# 2_2_128x32_OLED-SPI-DRO-FTDI-6.net
KiCad netlist of a schematic drawn in EAGLE
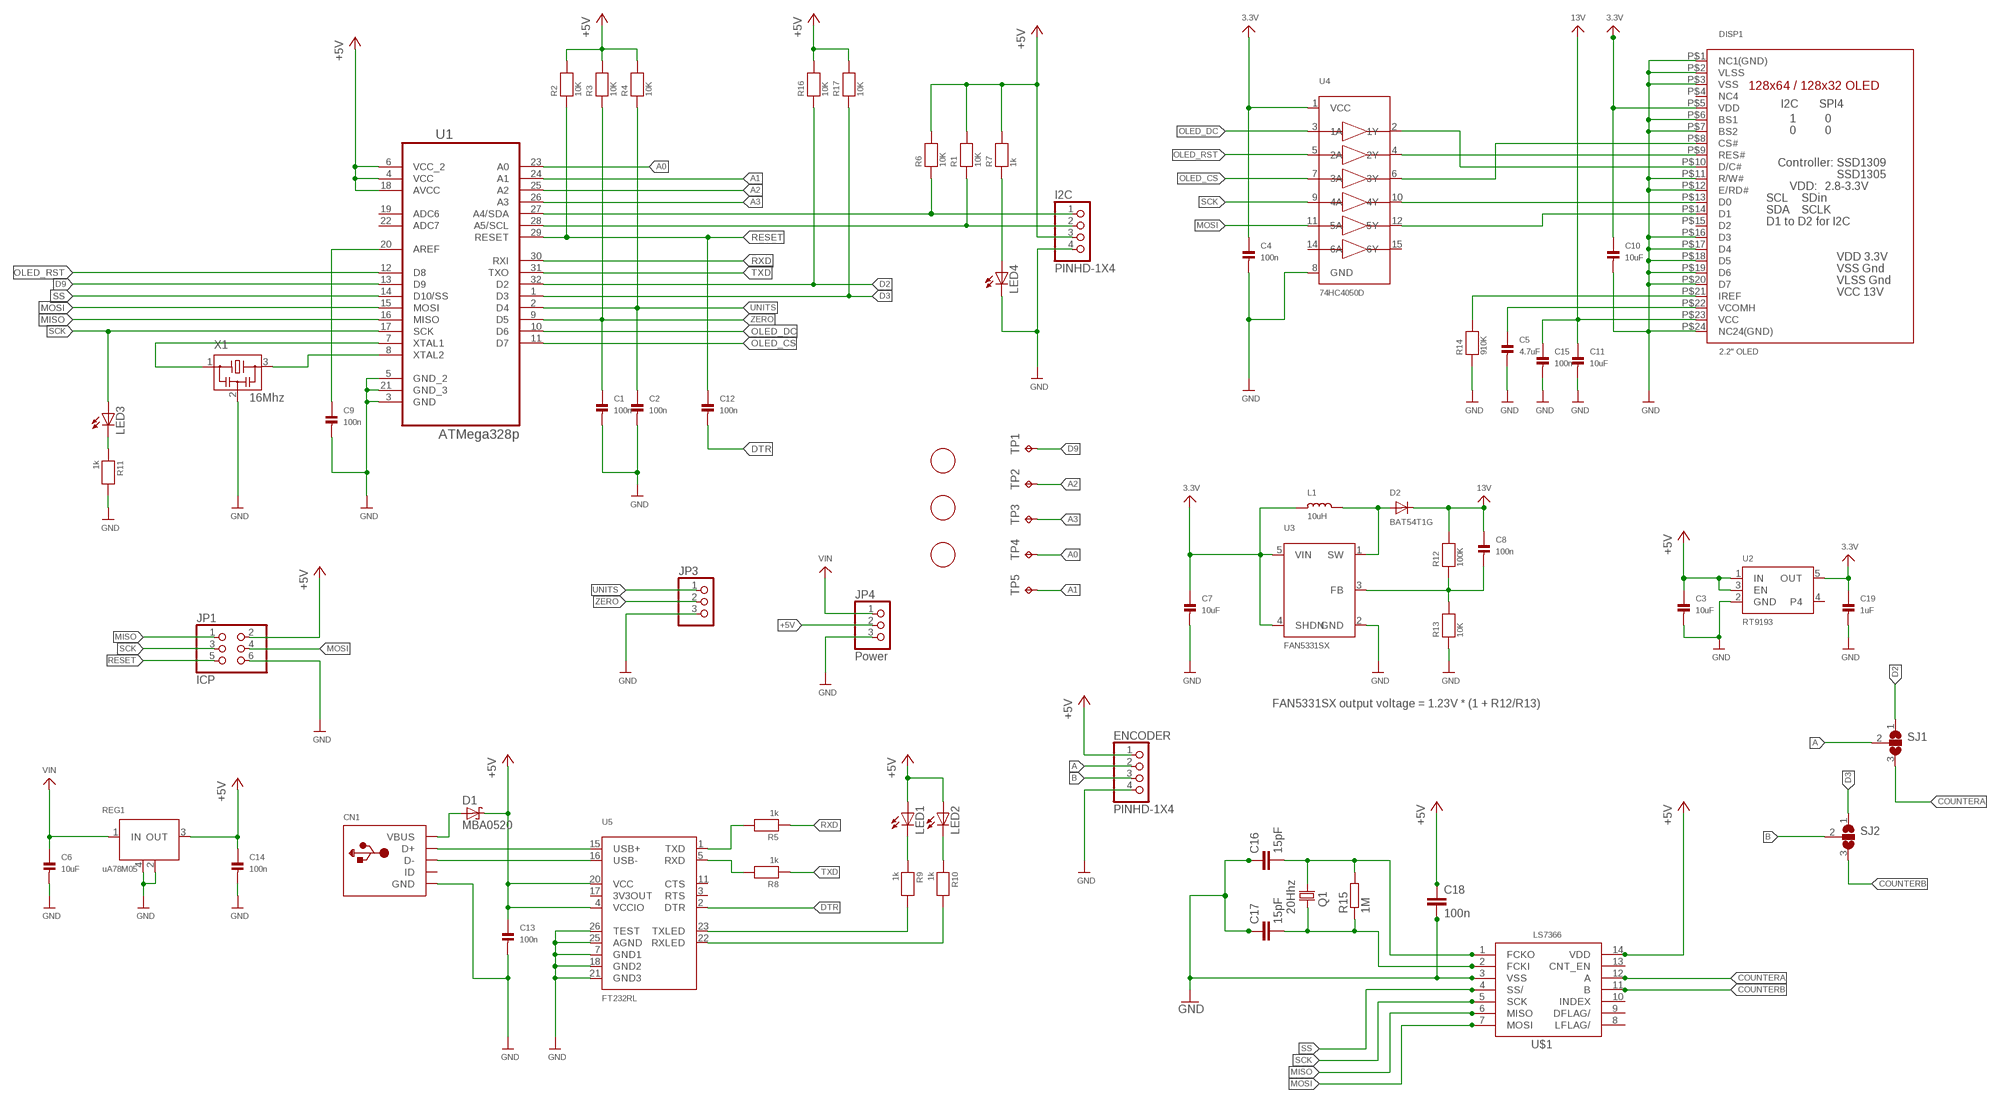
[diagram p0: schematic, sheet 1]

(export (version "E")
  (design (tool "Eeschema 10.0.6"))
  (components
    (comp (ref "C1")
      (value "100n")
      (footprint "eagle-import:0805")
      (libsource (lib "eagle-import") (part "CAP_CERAMIC0805"))
    )
    (comp (ref "C2")
      (value "100n")
      (footprint "eagle-import:0805")
      (libsource (lib "eagle-import") (part "CAP_CERAMIC0805"))
    )
    (comp (ref "C3")
      (value "10uF")
      (footprint "eagle-import:0805")
      (libsource (lib "eagle-import") (part "CAP_CERAMIC0805"))
    )
    (comp (ref "C4")
      (value "100n")
      (footprint "eagle-import:0805")
      (libsource (lib "eagle-import") (part "CAP_CERAMIC0805"))
    )
    (comp (ref "C5")
      (value "4.7uF")
      (footprint "eagle-import:0805")
      (libsource (lib "eagle-import") (part "CAP_CERAMIC0805"))
    )
    (comp (ref "C6")
      (value "10uF")
      (footprint "eagle-import:0805")
      (libsource (lib "eagle-import") (part "CAP_CERAMIC0805"))
    )
    (comp (ref "C7")
      (value "10uF")
      (footprint "eagle-import:0805")
      (libsource (lib "eagle-import") (part "CAP_CERAMIC0805"))
    )
    (comp (ref "C8")
      (value "100n")
      (footprint "eagle-import:0805")
      (libsource (lib "eagle-import") (part "CAP_CERAMIC0805"))
    )
    (comp (ref "C9")
      (value "100n")
      (footprint "eagle-import:0805")
      (libsource (lib "eagle-import") (part "CAP_CERAMIC0805"))
    )
    (comp (ref "C10")
      (value "10uF")
      (footprint "eagle-import:0805")
      (libsource (lib "eagle-import") (part "CAP_CERAMIC0805"))
    )
    (comp (ref "C11")
      (value "10uF")
      (footprint "eagle-import:0805")
      (libsource (lib "eagle-import") (part "CAP_CERAMIC0805"))
    )
    (comp (ref "C12")
      (value "100n")
      (footprint "eagle-import:0805")
      (libsource (lib "eagle-import") (part "CAP_CERAMIC0805"))
    )
    (comp (ref "C13")
      (value "100n")
      (footprint "eagle-import:0805")
      (libsource (lib "eagle-import") (part "CAP_CERAMIC0805"))
    )
    (comp (ref "C14")
      (value "100n")
      (footprint "eagle-import:0805")
      (libsource (lib "eagle-import") (part "CAP_CERAMIC0805"))
    )
    (comp (ref "C15")
      (value "100n")
      (footprint "eagle-import:0805")
      (libsource (lib "eagle-import") (part "CAP_CERAMIC0805"))
    )
    (comp (ref "C16")
      (value "15pF")
      (footprint "eagle-import:C0805")
      (libsource (lib "eagle-import") (part "C-EUC0805"))
    )
    (comp (ref "C17")
      (value "15pF")
      (footprint "eagle-import:C0805")
      (libsource (lib "eagle-import") (part "C-EUC0805"))
    )
    (comp (ref "C18")
      (value "100n")
      (footprint "eagle-import:C0805")
      (libsource (lib "eagle-import") (part "C-EUC0805"))
    )
    (comp (ref "C19")
      (value "1uF")
      (footprint "eagle-import:0805")
      (libsource (lib "eagle-import") (part "CAP_CERAMIC0805"))
    )
    (comp (ref "CN1")
      (value "USBMINIB")
      (footprint "eagle-import:USB-MINIB")
      (libsource (lib "eagle-import") (part "USBMINIB"))
    )
    (comp (ref "D1")
      (value "MBA0520")
      (footprint "eagle-import:SOD123")
      (libsource (lib "eagle-import") (part "MBR0520"))
    )
    (comp (ref "D2")
      (value "BAT54T1G")
      (footprint "eagle-import:SOD-123")
      (libsource (lib "eagle-import") (part "DIODESOD-123"))
    )
    (comp (ref "DISP1")
      (value "2.2\" OLED")
      (footprint "eagle-import:1.5-128X64-TOP-CONTACT")
      (libsource (lib "eagle-import") (part "1.5-128X64-OLED"))
    )
    (comp (ref "ENCODER")
      (value "PINHD-1X4")
      (footprint "eagle-import:1X04-BIG")
      (libsource (lib "eagle-import") (part "PINHD-1X4"))
    )
    (comp (ref "I2C")
      (value "PINHD-1X4")
      (footprint "eagle-import:1X04-BIG")
      (libsource (lib "eagle-import") (part "PINHD-1X4"))
    )
    (comp (ref "JP1")
      (value "ICP")
      (footprint "eagle-import:2X03")
      (libsource (lib "eagle-import") (part "PINHD-2X3"))
    )
    (comp (ref "JP3")
      (value "PINHD-1X3")
      (footprint "eagle-import:1X03")
      (libsource (lib "eagle-import") (part "PINHD-1X3"))
    )
    (comp (ref "JP4")
      (value "Power")
      (footprint "eagle-import:1X03")
      (libsource (lib "eagle-import") (part "PINHD-1X3"))
    )
    (comp (ref "L1")
      (value "10uH")
      (footprint "eagle-import:INDUCTOR_1007")
      (libsource (lib "eagle-import") (part "INDUCTOR"))
    )
    (comp (ref "LED1")
      (value "LEDCHIPLED_0805")
      (footprint "eagle-import:CHIPLED_0805")
      (libsource (lib "eagle-import") (part "LEDCHIPLED_0805"))
    )
    (comp (ref "LED2")
      (value "LEDCHIPLED_0805")
      (footprint "eagle-import:CHIPLED_0805")
      (libsource (lib "eagle-import") (part "LEDCHIPLED_0805"))
    )
    (comp (ref "LED3")
      (value "LEDCHIPLED_0805")
      (footprint "eagle-import:CHIPLED_0805")
      (libsource (lib "eagle-import") (part "LEDCHIPLED_0805"))
    )
    (comp (ref "LED4")
      (value "LEDCHIPLED_0805")
      (footprint "eagle-import:CHIPLED_0805")
      (libsource (lib "eagle-import") (part "LEDCHIPLED_0805"))
    )
    (comp (ref "Q1")
      (value "20Hhz")
      (footprint "eagle-import:F6-XTAL")
      (libsource (lib "eagle-import") (part "F6-CRYSTAL"))
    )
    (comp (ref "R1")
      (value "10K")
      (footprint "eagle-import:0805")
      (libsource (lib "eagle-import") (part "RESISTOR0805"))
    )
    (comp (ref "R2")
      (value "10K")
      (footprint "eagle-import:0805")
      (libsource (lib "eagle-import") (part "RESISTOR0805"))
    )
    (comp (ref "R3")
      (value "10K")
      (footprint "eagle-import:0805")
      (libsource (lib "eagle-import") (part "RESISTOR0805"))
    )
    (comp (ref "R4")
      (value "10K")
      (footprint "eagle-import:0805")
      (libsource (lib "eagle-import") (part "RESISTOR0805"))
    )
    (comp (ref "R5")
      (value "1k")
      (footprint "eagle-import:0805")
      (libsource (lib "eagle-import") (part "RESISTOR0805"))
    )
    (comp (ref "R6")
      (value "10K")
      (footprint "eagle-import:0805")
      (libsource (lib "eagle-import") (part "RESISTOR0805"))
    )
    (comp (ref "R7")
      (value "1k")
      (footprint "eagle-import:0805")
      (libsource (lib "eagle-import") (part "RESISTOR0805"))
    )
    (comp (ref "R8")
      (value "1k")
      (footprint "eagle-import:0805")
      (libsource (lib "eagle-import") (part "RESISTOR0805"))
    )
    (comp (ref "R9")
      (value "1k")
      (footprint "eagle-import:0805")
      (libsource (lib "eagle-import") (part "RESISTOR0805"))
    )
    (comp (ref "R10")
      (value "1k")
      (footprint "eagle-import:0805")
      (libsource (lib "eagle-import") (part "RESISTOR0805"))
    )
    (comp (ref "R11")
      (value "1k")
      (footprint "eagle-import:0805")
      (libsource (lib "eagle-import") (part "RESISTOR0805"))
    )
    (comp (ref "R12")
      (value "100K")
      (footprint "eagle-import:0805")
      (libsource (lib "eagle-import") (part "RESISTOR0805"))
    )
    (comp (ref "R13")
      (value "10K")
      (footprint "eagle-import:0805")
      (libsource (lib "eagle-import") (part "RESISTOR0805"))
    )
    (comp (ref "R14")
      (value "910K")
      (footprint "eagle-import:0805")
      (libsource (lib "eagle-import") (part "RESISTOR0805"))
    )
    (comp (ref "R15")
      (value "1M")
      (footprint "eagle-import:M0805")
      (libsource (lib "eagle-import") (part "R-EU_M0805"))
    )
    (comp (ref "R16")
      (value "10K")
      (footprint "eagle-import:0805")
      (libsource (lib "eagle-import") (part "RESISTOR0805"))
    )
    (comp (ref "R17")
      (value "10K")
      (footprint "eagle-import:0805")
      (libsource (lib "eagle-import") (part "RESISTOR0805"))
    )
    (comp (ref "REG1")
      (value "uA78M05")
      (footprint "eagle-import:UA78M05")
      (libsource (lib "eagle-import") (part "UA78M05"))
    )
    (comp (ref "SJ1")
      (value "SJ2W")
      (footprint "eagle-import:SJ_2")
      (libsource (lib "eagle-import") (part "SJ2W"))
    )
    (comp (ref "SJ2")
      (value "SJ2W")
      (footprint "eagle-import:SJ_2")
      (libsource (lib "eagle-import") (part "SJ2W"))
    )
    (comp (ref "TP1")
      (value "TPTP08R")
      (footprint "eagle-import:TP08R")
      (libsource (lib "eagle-import") (part "TPTP08R"))
    )
    (comp (ref "TP2")
      (value "TPTP08R")
      (footprint "eagle-import:TP08R")
      (libsource (lib "eagle-import") (part "TPTP08R"))
    )
    (comp (ref "TP3")
      (value "TPTP08R")
      (footprint "eagle-import:TP08R")
      (libsource (lib "eagle-import") (part "TPTP08R"))
    )
    (comp (ref "TP4")
      (value "TPTP08R")
      (footprint "eagle-import:TP08R")
      (libsource (lib "eagle-import") (part "TPTP08R"))
    )
    (comp (ref "TP5")
      (value "TPTP08R")
      (footprint "eagle-import:TP08R")
      (libsource (lib "eagle-import") (part "TPTP08R"))
    )
    (comp (ref "U$1")
      (value "LS7366")
      (footprint "eagle-import:SO14")
      (libsource (lib "eagle-import") (part "LS7366"))
    )
    (comp (ref "U$2")
      (value "FIDUCIAL")
      (footprint "eagle-import:FIDUCIAL_1MM")
      (libsource (lib "eagle-import") (part "FIDUCIAL"))
    )
    (comp (ref "U$6")
      (value "FIDUCIAL")
      (footprint "eagle-import:FIDUCIAL_1MM")
      (libsource (lib "eagle-import") (part "FIDUCIAL"))
    )
    (comp (ref "U$28")
      (value "FIDUCIAL")
      (footprint "eagle-import:FIDUCIAL_1MM")
      (libsource (lib "eagle-import") (part "FIDUCIAL"))
    )
    (comp (ref "U1")
      (value "ATMega328p")
      (footprint "eagle-import:TQFP-32")
      (libsource (lib "eagle-import") (part "ATMEGA328P-AU"))
    )
    (comp (ref "U2")
      (value "RT9193")
      (footprint "eagle-import:SOT23-5")
      (libsource (lib "eagle-import") (part "VREG_SOT23-5"))
    )
    (comp (ref "U3")
      (value "FAN5331SX")
      (footprint "eagle-import:SOT23-5")
      (libsource (lib "eagle-import") (part "FAN5331"))
    )
    (comp (ref "U4")
      (value "74HC4050D")
      (footprint "eagle-import:SOIC16")
      (libsource (lib "eagle-import") (part "74HC4050D"))
    )
    (comp (ref "U5")
      (value "FT232RL")
      (footprint "eagle-import:SSOP28DB")
      (libsource (lib "eagle-import") (part "FT232RLSSOP28"))
    )
    (comp (ref "X1")
      (value "16Mhz")
      (footprint "eagle-import:CSTCE-CRYSTAL-OSC")
      (libsource (lib "eagle-import") (part "CSTCE-CRYSTAL-OSC"))
    )
  )
  (nets
    (net (code "1") (name "+5V") (class "Default")
      (node (ref "C13") (pin "1") (pinfunction "P$1_1") (pintype "passive"))
      (node (ref "C14") (pin "1") (pinfunction "P$1_1") (pintype "passive"))
      (node (ref "C18") (pin "1") (pinfunction "1_1") (pintype "passive"))
      (node (ref "C3") (pin "1") (pinfunction "P$1_1") (pintype "passive"))
      (node (ref "D1") (pin "C") (pinfunction "C_C") (pintype "passive"))
      (node (ref "ENCODER") (pin "1") (pinfunction "1_1") (pintype "passive"))
      (node (ref "I2C") (pin "3") (pinfunction "3_3") (pintype "passive"))
      (node (ref "JP1") (pin "2") (pinfunction "2_2") (pintype "passive"))
      (node (ref "JP4") (pin "2") (pinfunction "2_2") (pintype "passive"))
      (node (ref "LED1") (pin "A") (pinfunction "A_A") (pintype "passive"))
      (node (ref "LED2") (pin "A") (pinfunction "A_A") (pintype "passive"))
      (node (ref "R1") (pin "2") (pinfunction "2_2") (pintype "passive"))
      (node (ref "R16") (pin "2") (pinfunction "2_2") (pintype "passive"))
      (node (ref "R17") (pin "2") (pinfunction "2_2") (pintype "passive"))
      (node (ref "R2") (pin "2") (pinfunction "2_2") (pintype "passive"))
      (node (ref "R3") (pin "2") (pinfunction "2_2") (pintype "passive"))
      (node (ref "R4") (pin "2") (pinfunction "2_2") (pintype "passive"))
      (node (ref "R6") (pin "2") (pinfunction "2_2") (pintype "passive"))
      (node (ref "R7") (pin "2") (pinfunction "2_2") (pintype "passive"))
      (node (ref "REG1") (pin "3") (pinfunction "OUT_3") (pintype "passive"))
      (node (ref "U$1") (pin "14") (pinfunction "VDD_14") (pintype "power_in"))
      (node (ref "U1") (pin "18") (pinfunction "AVCC_18") (pintype "power_in"))
      (node (ref "U1") (pin "4") (pinfunction "VCC_4") (pintype "power_in"))
      (node (ref "U1") (pin "6") (pinfunction "VCC_2_6") (pintype "power_in"))
      (node (ref "U2") (pin "1") (pinfunction "IN_1") (pintype "bidirectional"))
      (node (ref "U2") (pin "3") (pinfunction "EN_3") (pintype "bidirectional"))
      (node (ref "U5") (pin "20") (pinfunction "VCC_20") (pintype "power_in"))
      (node (ref "U5") (pin "4") (pinfunction "VCCIO_4") (pintype "power_in"))
    )
    (net (code "2") (name "/3V3OUT") (class "Default")
      (node (ref "U5") (pin "17") (pinfunction "3V3OUT_17") (pintype "power_in"))
    )
    (net (code "3") (name "3.3V") (class "Default")
      (node (ref "C10") (pin "1") (pinfunction "P$1_1") (pintype "passive"))
      (node (ref "C19") (pin "1") (pinfunction "P$1_1") (pintype "passive"))
      (node (ref "C4") (pin "1") (pinfunction "P$1_1") (pintype "passive"))
      (node (ref "C7") (pin "1") (pinfunction "P$1_1") (pintype "passive"))
      (node (ref "DISP1") (pin "P$5") (pinfunction "VDD_P$5") (pintype "power_in"))
      (node (ref "L1") (pin "P$1") (pinfunction "1_P$1") (pintype "passive"))
      (node (ref "U2") (pin "5") (pinfunction "OUT_5") (pintype "bidirectional"))
      (node (ref "U3") (pin "4") (pinfunction "SHDN_4") (pintype "bidirectional"))
      (node (ref "U3") (pin "5") (pinfunction "VIN_5") (pintype "bidirectional"))
      (node (ref "U4") (pin "1") (pinfunction "VCC_1") (pintype "bidirectional"))
    )
    (net (code "4") (name "13V") (class "Default")
      (node (ref "C11") (pin "1") (pinfunction "P$1_1") (pintype "passive"))
      (node (ref "C15") (pin "1") (pinfunction "P$1_1") (pintype "passive"))
      (node (ref "C8") (pin "1") (pinfunction "P$1_1") (pintype "passive"))
      (node (ref "D2") (pin "C") (pinfunction "C_C") (pintype "passive"))
      (node (ref "DISP1") (pin "P$23") (pinfunction "VCC_P$23") (pintype "power_in"))
      (node (ref "R12") (pin "2") (pinfunction "2_2") (pintype "passive"))
    )
    (net (code "5") (name "A") (class "Default")
      (node (ref "ENCODER") (pin "2") (pinfunction "2_2") (pintype "passive"))
      (node (ref "SJ1") (pin "2") (pinfunction "2_2") (pintype "passive"))
    )
    (net (code "6") (name "A0") (class "Default")
      (node (ref "TP4") (pin "TP") (pinfunction "TP_TP") (pintype "input"))
      (node (ref "U1") (pin "23") (pinfunction "A0_23") (pintype "bidirectional"))
    )
    (net (code "7") (name "A1") (class "Default")
      (node (ref "TP5") (pin "TP") (pinfunction "TP_TP") (pintype "input"))
      (node (ref "U1") (pin "24") (pinfunction "A1_24") (pintype "bidirectional"))
    )
    (net (code "8") (name "A2") (class "Default")
      (node (ref "TP2") (pin "TP") (pinfunction "TP_TP") (pintype "input"))
      (node (ref "U1") (pin "25") (pinfunction "A2_25") (pintype "bidirectional"))
    )
    (net (code "9") (name "A3") (class "Default")
      (node (ref "TP3") (pin "TP") (pinfunction "TP_TP") (pintype "input"))
      (node (ref "U1") (pin "26") (pinfunction "A3_26") (pintype "bidirectional"))
    )
    (net (code "10") (name "B") (class "Default")
      (node (ref "ENCODER") (pin "3") (pinfunction "3_3") (pintype "passive"))
      (node (ref "SJ2") (pin "2") (pinfunction "2_2") (pintype "passive"))
    )
    (net (code "11") (name "COUNTERA") (class "Default")
      (node (ref "SJ1") (pin "3") (pinfunction "3_3") (pintype "passive"))
      (node (ref "U$1") (pin "12") (pinfunction "A_12") (pintype "bidirectional"))
    )
    (net (code "12") (name "COUNTERB") (class "Default")
      (node (ref "SJ2") (pin "3") (pinfunction "3_3") (pintype "passive"))
      (node (ref "U$1") (pin "11") (pinfunction "B_11") (pintype "bidirectional"))
    )
    (net (code "13") (name "D2") (class "Default")
      (node (ref "R16") (pin "1") (pinfunction "1_1") (pintype "passive"))
      (node (ref "SJ1") (pin "1") (pinfunction "1_1") (pintype "passive"))
      (node (ref "U1") (pin "32") (pinfunction "D2_32") (pintype "bidirectional"))
    )
    (net (code "14") (name "D3") (class "Default")
      (node (ref "R17") (pin "1") (pinfunction "1_1") (pintype "passive"))
      (node (ref "SJ2") (pin "1") (pinfunction "1_1") (pintype "passive"))
      (node (ref "U1") (pin "1") (pinfunction "D3_1") (pintype "bidirectional"))
    )
    (net (code "15") (name "D9") (class "Default")
      (node (ref "TP1") (pin "TP") (pinfunction "TP_TP") (pintype "input"))
      (node (ref "U1") (pin "13") (pinfunction "D9_13") (pintype "bidirectional"))
    )
    (net (code "16") (name "DTR") (class "Default")
      (node (ref "C12") (pin "2") (pinfunction "P$2_2") (pintype "passive"))
      (node (ref "U5") (pin "2") (pinfunction "DTR_2") (pintype "bidirectional"))
    )
    (net (code "17") (name "GND") (class "Default")
      (node (ref "C1") (pin "2") (pinfunction "P$2_2") (pintype "passive"))
      (node (ref "C10") (pin "2") (pinfunction "P$2_2") (pintype "passive"))
      (node (ref "C11") (pin "2") (pinfunction "P$2_2") (pintype "passive"))
      (node (ref "C13") (pin "2") (pinfunction "P$2_2") (pintype "passive"))
      (node (ref "C14") (pin "2") (pinfunction "P$2_2") (pintype "passive"))
      (node (ref "C15") (pin "2") (pinfunction "P$2_2") (pintype "passive"))
      (node (ref "C16") (pin "1") (pinfunction "1_1") (pintype "passive"))
      (node (ref "C17") (pin "1") (pinfunction "1_1") (pintype "passive"))
      (node (ref "C18") (pin "2") (pinfunction "2_2") (pintype "passive"))
      (node (ref "C19") (pin "2") (pinfunction "P$2_2") (pintype "passive"))
      (node (ref "C2") (pin "2") (pinfunction "P$2_2") (pintype "passive"))
      (node (ref "C3") (pin "2") (pinfunction "P$2_2") (pintype "passive"))
      (node (ref "C4") (pin "2") (pinfunction "P$2_2") (pintype "passive"))
      (node (ref "C5") (pin "2") (pinfunction "P$2_2") (pintype "passive"))
      (node (ref "C6") (pin "2") (pinfunction "P$2_2") (pintype "passive"))
      (node (ref "C7") (pin "2") (pinfunction "P$2_2") (pintype "passive"))
      (node (ref "C9") (pin "2") (pinfunction "P$2_2") (pintype "passive"))
      (node (ref "CN1") (pin "GND") (pinfunction "GND_GND") (pintype "power_in"))
      (node (ref "DISP1") (pin "P$1") (pinfunction "NC1(GND)_P$1") (pintype "bidirectional"))
      (node (ref "DISP1") (pin "P$11") (pinfunction "R/W#_P$11") (pintype "bidirectional"))
      (node (ref "DISP1") (pin "P$12") (pinfunction "E/RD#_P$12") (pintype "bidirectional"))
      (node (ref "DISP1") (pin "P$16") (pinfunction "D3_P$16") (pintype "input"))
      (node (ref "DISP1") (pin "P$17") (pinfunction "D4_P$17") (pintype "input"))
      (node (ref "DISP1") (pin "P$18") (pinfunction "D5_P$18") (pintype "bidirectional"))
      (node (ref "DISP1") (pin "P$19") (pinfunction "D6_P$19") (pintype "bidirectional"))
      (node (ref "DISP1") (pin "P$2") (pinfunction "VLSS_P$2") (pintype "power_in"))
      (node (ref "DISP1") (pin "P$20") (pinfunction "D7_P$20") (pintype "bidirectional"))
      (node (ref "DISP1") (pin "P$24") (pinfunction "NC24(GND)_P$24") (pintype "bidirectional"))
      (node (ref "DISP1") (pin "P$3") (pinfunction "VSS_P$3") (pintype "power_in"))
      (node (ref "DISP1") (pin "P$6") (pinfunction "BS1_P$6") (pintype "bidirectional"))
      (node (ref "DISP1") (pin "P$7") (pinfunction "BS2_P$7") (pintype "bidirectional"))
      (node (ref "ENCODER") (pin "4") (pinfunction "4_4") (pintype "passive"))
      (node (ref "I2C") (pin "4") (pinfunction "4_4") (pintype "passive"))
      (node (ref "JP1") (pin "6") (pinfunction "6_6") (pintype "passive"))
      (node (ref "JP3") (pin "3") (pinfunction "3_3") (pintype "passive"))
      (node (ref "JP4") (pin "3") (pinfunction "3_3") (pintype "passive"))
      (node (ref "LED4") (pin "C") (pinfunction "C_C") (pintype "passive"))
      (node (ref "R11") (pin "2") (pinfunction "2_2") (pintype "passive"))
      (node (ref "R13") (pin "1") (pinfunction "1_1") (pintype "passive"))
      (node (ref "R14") (pin "1") (pinfunction "1_1") (pintype "passive"))
      (node (ref "REG1") (pin "2") (pinfunction "COMMON1_2") (pintype "passive"))
      (node (ref "REG1") (pin "4") (pinfunction "COMMON2_4") (pintype "passive"))
      (node (ref "U$1") (pin "3") (pinfunction "VSS_3") (pintype "power_in"))
      (node (ref "U1") (pin "21") (pinfunction "GND_3_21") (pintype "passive"))
      (node (ref "U1") (pin "3") (pinfunction "GND_3") (pintype "passive"))
      (node (ref "U1") (pin "5") (pinfunction "GND_2_5") (pintype "passive"))
      (node (ref "U2") (pin "2") (pinfunction "GND_2") (pintype "bidirectional"))
      (node (ref "U3") (pin "2") (pinfunction "GND_2") (pintype "bidirectional"))
      (node (ref "U4") (pin "8") (pinfunction "GND_8") (pintype "bidirectional"))
      (node (ref "U5") (pin "18") (pinfunction "GND2_18") (pintype "power_in"))
      (node (ref "U5") (pin "21") (pinfunction "GND3_21") (pintype "power_in"))
      (node (ref "U5") (pin "25") (pinfunction "AGND_25") (pintype "power_in"))
      (node (ref "U5") (pin "26") (pinfunction "TEST_26") (pintype "input"))
      (node (ref "U5") (pin "7") (pinfunction "GND1_7") (pintype "power_in"))
      (node (ref "X1") (pin "2") (pinfunction "2_2") (pintype "passive"))
    )
    (net (code "18") (name "MISO") (class "Default")
      (node (ref "JP1") (pin "1") (pinfunction "1_1") (pintype "passive"))
      (node (ref "U$1") (pin "6") (pinfunction "MISO_6") (pintype "output"))
      (node (ref "U1") (pin "16") (pinfunction "MISO_16") (pintype "bidirectional"))
    )
    (net (code "19") (name "MOSI") (class "Default")
      (node (ref "JP1") (pin "4") (pinfunction "4_4") (pintype "passive"))
      (node (ref "U$1") (pin "7") (pinfunction "MOSI_7") (pintype "input"))
      (node (ref "U1") (pin "15") (pinfunction "MOSI_15") (pintype "bidirectional"))
      (node (ref "U4") (pin "11") (pinfunction "5A_11") (pintype "bidirectional"))
    )
    (net (code "20") (name "Net-(C5-P$1)") (class "Default")
      (node (ref "C5") (pin "1") (pinfunction "P$1_1") (pintype "passive"))
      (node (ref "DISP1") (pin "P$22") (pinfunction "VCOMH_P$22") (pintype "bidirectional"))
    )
    (net (code "21") (name "Net-(C8-P$2)") (class "Default")
      (node (ref "C8") (pin "2") (pinfunction "P$2_2") (pintype "passive"))
      (node (ref "R12") (pin "1") (pinfunction "1_1") (pintype "passive"))
      (node (ref "R13") (pin "2") (pinfunction "2_2") (pintype "passive"))
      (node (ref "U3") (pin "3") (pinfunction "FB_3") (pintype "bidirectional"))
    )
    (net (code "22") (name "Net-(C9-P$1)") (class "Default")
      (node (ref "C9") (pin "1") (pinfunction "P$1_1") (pintype "passive"))
      (node (ref "U1") (pin "20") (pinfunction "AREF_20") (pintype "input"))
    )
    (net (code "23") (name "Net-(CN1-PadVBUS)") (class "Default")
      (node (ref "CN1") (pin "VBUS") (pinfunction "VBUS_VBUS") (pintype "power_in"))
      (node (ref "D1") (pin "A") (pinfunction "A_A") (pintype "passive"))
    )
    (net (code "24") (name "Net-(DISP1-CS#)") (class "Default")
      (node (ref "DISP1") (pin "P$8") (pinfunction "CS#_P$8") (pintype "bidirectional"))
      (node (ref "U4") (pin "6") (pinfunction "3Y_6") (pintype "bidirectional"))
    )
    (net (code "25") (name "Net-(DISP1-D0)") (class "Default")
      (node (ref "DISP1") (pin "P$13") (pinfunction "D0_P$13") (pintype "input"))
      (node (ref "U4") (pin "10") (pinfunction "4Y_10") (pintype "bidirectional"))
    )
    (net (code "26") (name "Net-(DISP1-D1)") (class "Default")
      (node (ref "DISP1") (pin "P$14") (pinfunction "D1_P$14") (pintype "input"))
      (node (ref "U4") (pin "12") (pinfunction "5Y_12") (pintype "bidirectional"))
    )
    (net (code "27") (name "Net-(DISP1-D{slash}C#)") (class "Default")
      (node (ref "DISP1") (pin "P$10") (pinfunction "D/C#_P$10") (pintype "bidirectional"))
      (node (ref "U4") (pin "2") (pinfunction "1Y_2") (pintype "bidirectional"))
    )
    (net (code "28") (name "Net-(DISP1-IREF)") (class "Default")
      (node (ref "DISP1") (pin "P$21") (pinfunction "IREF_P$21") (pintype "bidirectional"))
      (node (ref "R14") (pin "2") (pinfunction "2_2") (pintype "passive"))
    )
    (net (code "29") (name "Net-(DISP1-RES#)") (class "Default")
      (node (ref "DISP1") (pin "P$9") (pinfunction "RES#_P$9") (pintype "bidirectional"))
      (node (ref "U4") (pin "4") (pinfunction "2Y_4") (pintype "bidirectional"))
    )
    (net (code "30") (name "Net-(L1-2)") (class "Default")
      (node (ref "D2") (pin "A") (pinfunction "A_A") (pintype "passive"))
      (node (ref "L1") (pin "P$2") (pinfunction "2_P$2") (pintype "passive"))
      (node (ref "U3") (pin "1") (pinfunction "SW_1") (pintype "bidirectional"))
    )
    (net (code "31") (name "Net-(LED1-PadC)") (class "Default")
      (node (ref "LED1") (pin "C") (pinfunction "C_C") (pintype "passive"))
      (node (ref "R9") (pin "1") (pinfunction "1_1") (pintype "passive"))
    )
    (net (code "32") (name "Net-(LED2-PadC)") (class "Default")
      (node (ref "LED2") (pin "C") (pinfunction "C_C") (pintype "passive"))
      (node (ref "R10") (pin "1") (pinfunction "1_1") (pintype "passive"))
    )
    (net (code "33") (name "Net-(LED3-PadC)") (class "Default")
      (node (ref "LED3") (pin "C") (pinfunction "C_C") (pintype "passive"))
      (node (ref "R11") (pin "1") (pinfunction "1_1") (pintype "passive"))
    )
    (net (code "34") (name "Net-(LED4-PadA)") (class "Default")
      (node (ref "LED4") (pin "A") (pinfunction "A_A") (pintype "passive"))
      (node (ref "R7") (pin "1") (pinfunction "1_1") (pintype "passive"))
    )
    (net (code "35") (name "Net-(Q1-1)") (class "Default")
      (node (ref "C17") (pin "2") (pinfunction "2_2") (pintype "passive"))
      (node (ref "Q1") (pin "P$1") (pinfunction "1_P$1") (pintype "passive"))
      (node (ref "R15") (pin "1") (pinfunction "1_1") (pintype "passive"))
      (node (ref "U$1") (pin "2") (pinfunction "FCKI_2") (pintype "bidirectional"))
    )
    (net (code "36") (name "Net-(Q1-2)") (class "Default")
      (node (ref "C16") (pin "2") (pinfunction "2_2") (pintype "passive"))
      (node (ref "Q1") (pin "P$2") (pinfunction "2_P$2") (pintype "passive"))
      (node (ref "R15") (pin "2") (pinfunction "2_2") (pintype "passive"))
      (node (ref "U$1") (pin "1") (pinfunction "FCKO_1") (pintype "bidirectional"))
    )
    (net (code "37") (name "Net-(U1-A4{slash}SDA)") (class "Default")
      (node (ref "I2C") (pin "1") (pinfunction "1_1") (pintype "passive"))
      (node (ref "R6") (pin "1") (pinfunction "1_1") (pintype "passive"))
      (node (ref "U1") (pin "27") (pinfunction "A4/SDA_27") (pintype "bidirectional"))
    )
    (net (code "38") (name "Net-(U1-A5{slash}SCL)") (class "Default")
      (node (ref "I2C") (pin "2") (pinfunction "2_2") (pintype "passive"))
      (node (ref "R1") (pin "1") (pinfunction "1_1") (pintype "passive"))
      (node (ref "U1") (pin "28") (pinfunction "A5/SCL_28") (pintype "bidirectional"))
    )
    (net (code "39") (name "Net-(U1-XTAL1)") (class "Default")
      (node (ref "U1") (pin "7") (pinfunction "XTAL1_7") (pintype "bidirectional"))
      (node (ref "X1") (pin "1") (pinfunction "1_1") (pintype "passive"))
    )
    (net (code "40") (name "Net-(U1-XTAL2)") (class "Default")
      (node (ref "U1") (pin "8") (pinfunction "XTAL2_8") (pintype "bidirectional"))
      (node (ref "X1") (pin "3") (pinfunction "3_3") (pintype "passive"))
    )
    (net (code "41") (name "Net-(U5-RXD)") (class "Default")
      (node (ref "R8") (pin "2") (pinfunction "2_2") (pintype "passive"))
      (node (ref "U5") (pin "5") (pinfunction "RXD_5") (pintype "input"))
    )
    (net (code "42") (name "Net-(U5-RXLED)") (class "Default")
      (node (ref "R10") (pin "2") (pinfunction "2_2") (pintype "passive"))
      (node (ref "U5") (pin "22") (pinfunction "RXLED_22") (pintype "bidirectional"))
    )
    (net (code "43") (name "Net-(U5-TXD)") (class "Default")
      (node (ref "R5") (pin "2") (pinfunction "2_2") (pintype "passive"))
      (node (ref "U5") (pin "1") (pinfunction "TXD_1") (pintype "output"))
    )
    (net (code "44") (name "Net-(U5-TXLED)") (class "Default")
      (node (ref "R9") (pin "2") (pinfunction "2_2") (pintype "passive"))
      (node (ref "U5") (pin "23") (pinfunction "TXLED_23") (pintype "bidirectional"))
    )
    (net (code "45") (name "Net-(U5-USB+)") (class "Default")
      (node (ref "CN1") (pin "D+") (pinfunction "D+_D+") (pintype "bidirectional"))
      (node (ref "U5") (pin "15") (pinfunction "USB+_15") (pintype "bidirectional"))
    )
    (net (code "46") (name "Net-(U5-USB-)") (class "Default")
      (node (ref "CN1") (pin "D-") (pinfunction "D-_D-") (pintype "bidirectional"))
      (node (ref "U5") (pin "16") (pinfunction "USB-_16") (pintype "bidirectional"))
    )
    (net (code "47") (name "OLED_CS") (class "Default")
      (node (ref "U1") (pin "11") (pinfunction "D7_11") (pintype "bidirectional"))
      (node (ref "U4") (pin "7") (pinfunction "3A_7") (pintype "bidirectional"))
    )
    (net (code "48") (name "OLED_DC") (class "Default")
      (node (ref "U1") (pin "10") (pinfunction "D6_10") (pintype "bidirectional"))
      (node (ref "U4") (pin "3") (pinfunction "1A_3") (pintype "bidirectional"))
    )
    (net (code "49") (name "OLED_RST") (class "Default")
      (node (ref "U1") (pin "12") (pinfunction "D8_12") (pintype "bidirectional"))
      (node (ref "U4") (pin "5") (pinfunction "2A_5") (pintype "bidirectional"))
    )
    (net (code "50") (name "RESET") (class "Default")
      (node (ref "C12") (pin "1") (pinfunction "P$1_1") (pintype "passive"))
      (node (ref "JP1") (pin "5") (pinfunction "5_5") (pintype "passive"))
      (node (ref "R2") (pin "1") (pinfunction "1_1") (pintype "passive"))
      (node (ref "U1") (pin "29") (pinfunction "RESET_29") (pintype "bidirectional"))
    )
    (net (code "51") (name "RXD") (class "Default")
      (node (ref "R5") (pin "1") (pinfunction "1_1") (pintype "passive"))
      (node (ref "U1") (pin "30") (pinfunction "RXI_30") (pintype "bidirectional"))
    )
    (net (code "52") (name "SCK") (class "Default")
      (node (ref "JP1") (pin "3") (pinfunction "3_3") (pintype "passive"))
      (node (ref "LED3") (pin "A") (pinfunction "A_A") (pintype "passive"))
      (node (ref "U$1") (pin "5") (pinfunction "SCK_5") (pintype "bidirectional"))
      (node (ref "U1") (pin "17") (pinfunction "SCK_17") (pintype "bidirectional"))
      (node (ref "U4") (pin "9") (pinfunction "4A_9") (pintype "bidirectional"))
    )
    (net (code "53") (name "SS") (class "Default")
      (node (ref "U$1") (pin "4") (pinfunction "SS/_4") (pintype "bidirectional"))
      (node (ref "U1") (pin "14") (pinfunction "D10/SS_14") (pintype "bidirectional"))
    )
    (net (code "54") (name "TXD") (class "Default")
      (node (ref "R8") (pin "1") (pinfunction "1_1") (pintype "passive"))
      (node (ref "U1") (pin "31") (pinfunction "TXO_31") (pintype "bidirectional"))
    )
    (net (code "55") (name "UNITS") (class "Default")
      (node (ref "C2") (pin "1") (pinfunction "P$1_1") (pintype "passive"))
      (node (ref "JP3") (pin "1") (pinfunction "1_1") (pintype "passive"))
      (node (ref "R4") (pin "1") (pinfunction "1_1") (pintype "passive"))
      (node (ref "U1") (pin "2") (pinfunction "D4_2") (pintype "bidirectional"))
    )
    (net (code "56") (name "VIN") (class "Default")
      (node (ref "C6") (pin "1") (pinfunction "P$1_1") (pintype "passive"))
      (node (ref "JP4") (pin "1") (pinfunction "1_1") (pintype "passive"))
      (node (ref "REG1") (pin "1") (pinfunction "IN_1") (pintype "input"))
    )
    (net (code "57") (name "ZERO") (class "Default")
      (node (ref "C1") (pin "1") (pinfunction "P$1_1") (pintype "passive"))
      (node (ref "JP3") (pin "2") (pinfunction "2_2") (pintype "passive"))
      (node (ref "R3") (pin "1") (pinfunction "1_1") (pintype "passive"))
      (node (ref "U1") (pin "9") (pinfunction "D5_9") (pintype "bidirectional"))
    )
    (net (code "58") (name "unconnected-(CN1-PadID)") (class "Default")
      (node (ref "CN1") (pin "ID") (pinfunction "ID_ID") (pintype "bidirectional"))
    )
    (net (code "59") (name "unconnected-(DISP1-D2-PadP$15)") (class "Default")
      (node (ref "DISP1") (pin "P$15") (pinfunction "D2_P$15") (pintype "input"))
    )
    (net (code "60") (name "unconnected-(DISP1-NC4-PadP$4)") (class "Default")
      (node (ref "DISP1") (pin "P$4") (pinfunction "NC4_P$4") (pintype "no_connect"))
    )
    (net (code "61") (name "unconnected-(U$1-CNT_EN-Pad13)") (class "Default")
      (node (ref "U$1") (pin "13") (pinfunction "CNT_EN_13") (pintype "bidirectional"))
    )
    (net (code "62") (name "unconnected-(U$1-DFLAG{slash}-Pad9)") (class "Default")
      (node (ref "U$1") (pin "9") (pinfunction "DFLAG/_9") (pintype "output"))
    )
    (net (code "63") (name "unconnected-(U$1-INDEX-Pad10)") (class "Default")
      (node (ref "U$1") (pin "10") (pinfunction "INDEX_10") (pintype "bidirectional"))
    )
    (net (code "64") (name "unconnected-(U$1-LFLAG{slash}-Pad8)") (class "Default")
      (node (ref "U$1") (pin "8") (pinfunction "LFLAG/_8") (pintype "output"))
    )
    (net (code "65") (name "unconnected-(U1-ADC6-Pad19)") (class "Default")
      (node (ref "U1") (pin "19") (pinfunction "ADC6_19") (pintype "input"))
    )
    (net (code "66") (name "unconnected-(U1-ADC7-Pad22)") (class "Default")
      (node (ref "U1") (pin "22") (pinfunction "ADC7_22") (pintype "input"))
    )
    (net (code "67") (name "unconnected-(U2-P4-Pad4)") (class "Default")
      (node (ref "U2") (pin "4") (pinfunction "P4_4") (pintype "bidirectional"))
    )
    (net (code "68") (name "unconnected-(U4-6A-Pad14)") (class "Default")
      (node (ref "U4") (pin "14") (pinfunction "6A_14") (pintype "bidirectional"))
    )
    (net (code "69") (name "unconnected-(U4-6Y-Pad15)") (class "Default")
      (node (ref "U4") (pin "15") (pinfunction "6Y_15") (pintype "bidirectional"))
    )
    (net (code "70") (name "unconnected-(U5-CTS-Pad11)") (class "Default")
      (node (ref "U5") (pin "11") (pinfunction "CTS_11") (pintype "bidirectional"))
    )
    (net (code "71") (name "unconnected-(U5-RTS-Pad3)") (class "Default")
      (node (ref "U5") (pin "3") (pinfunction "RTS_3") (pintype "bidirectional"))
    )
  )
)
